# MD201x_2019-09-04.net
KiCad netlist of a schematic drawn in EAGLE
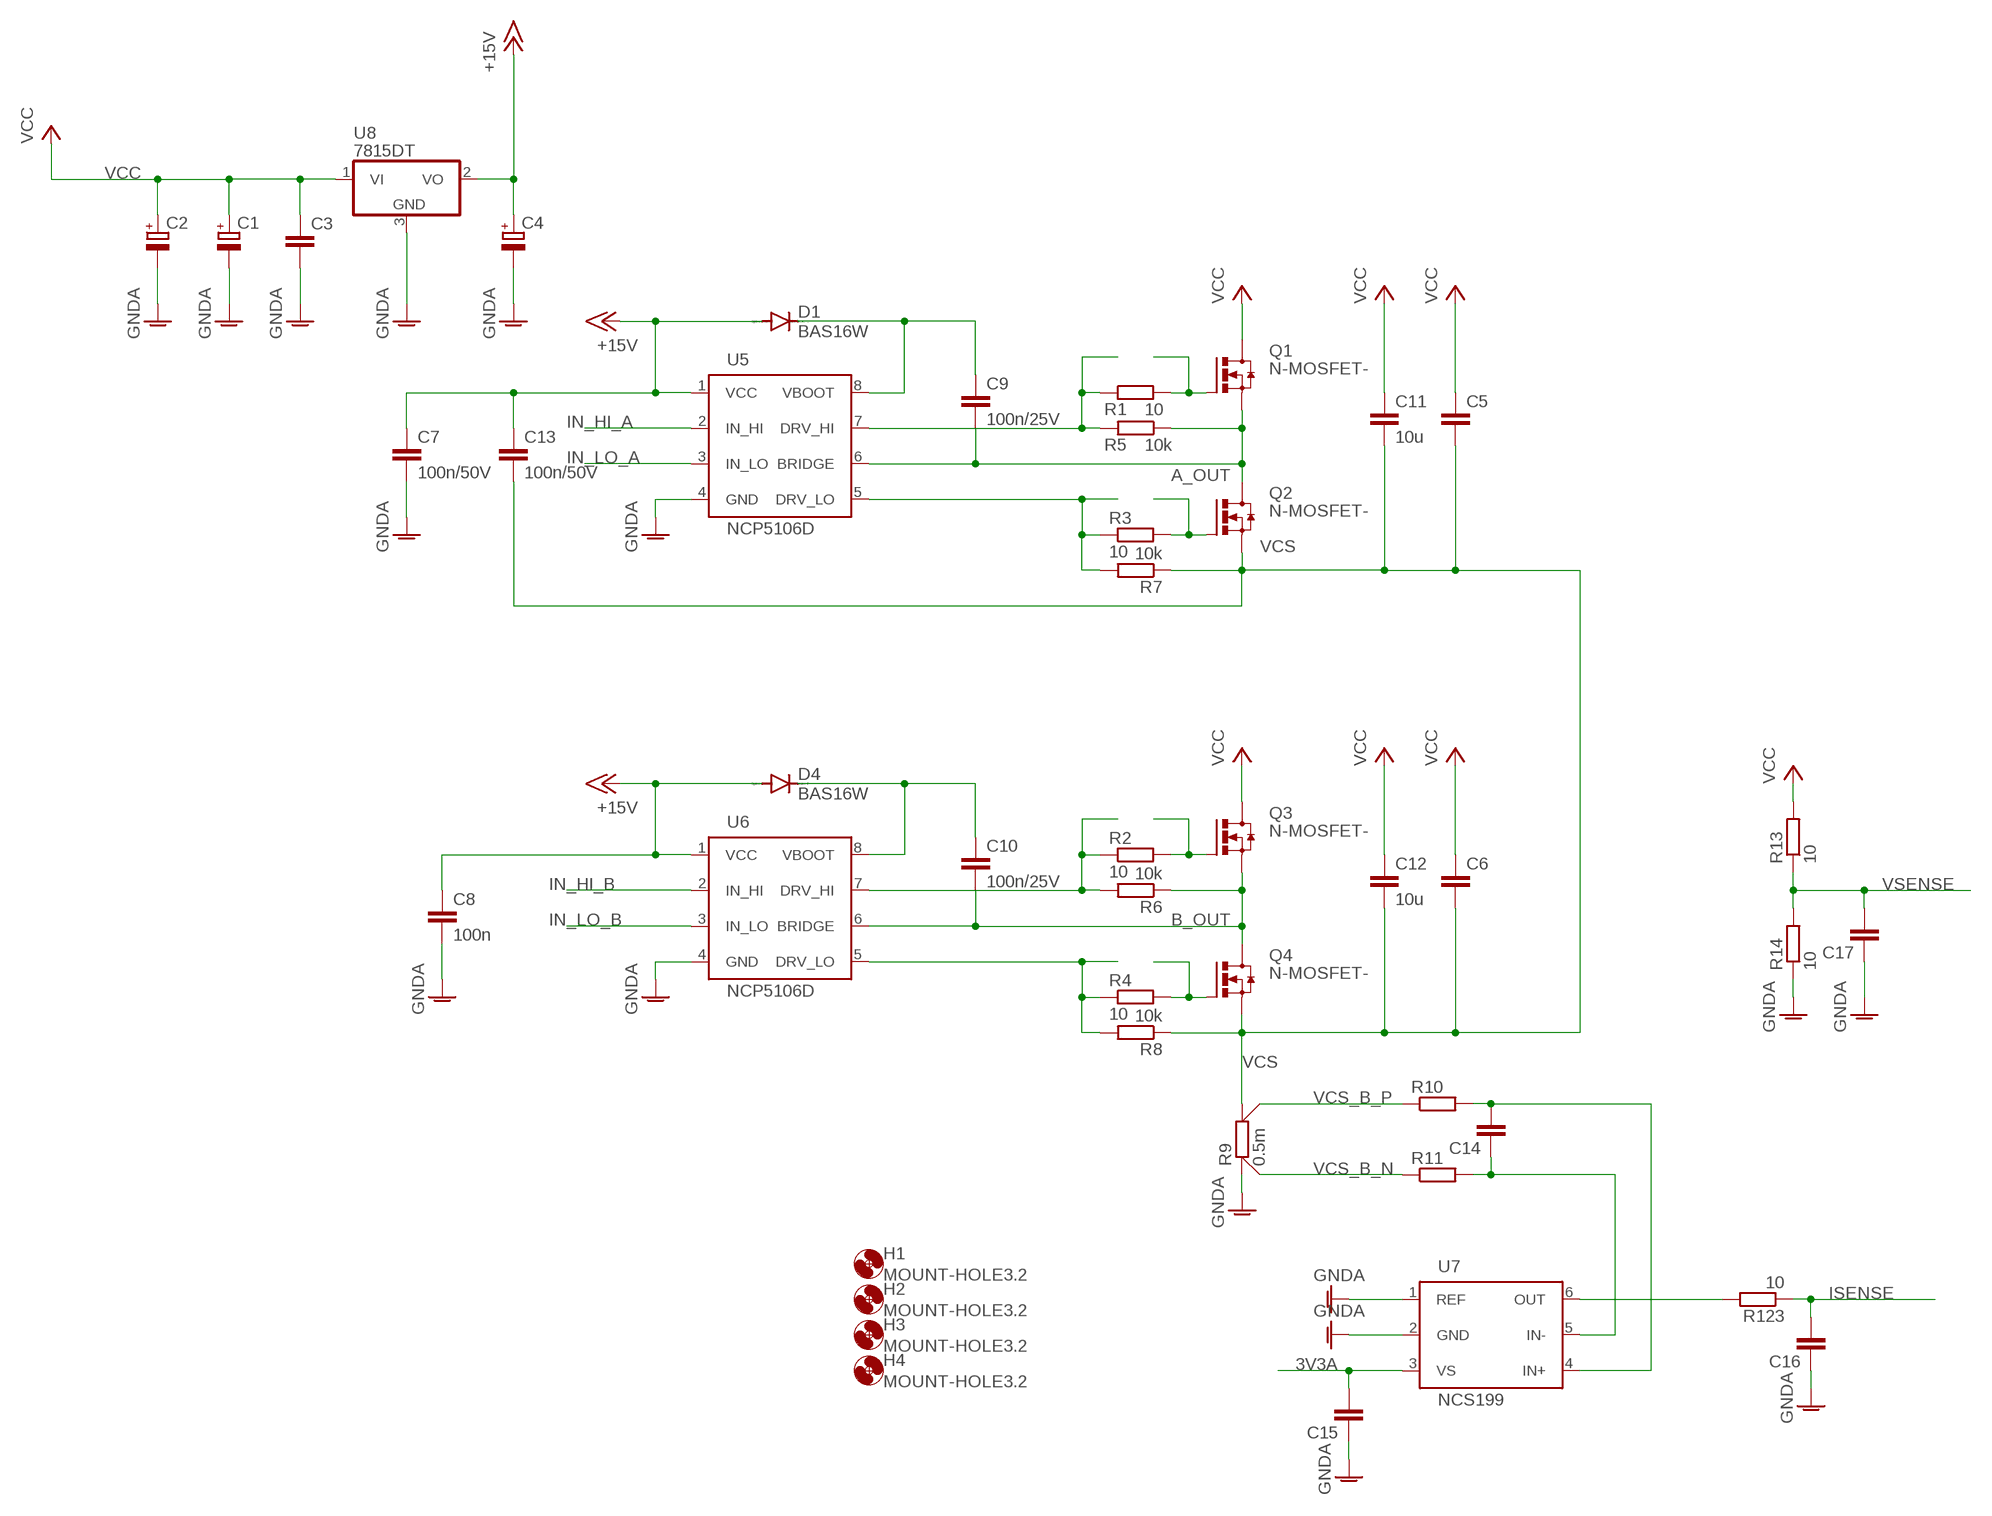
[diagram p0: schematic, sheet 1]
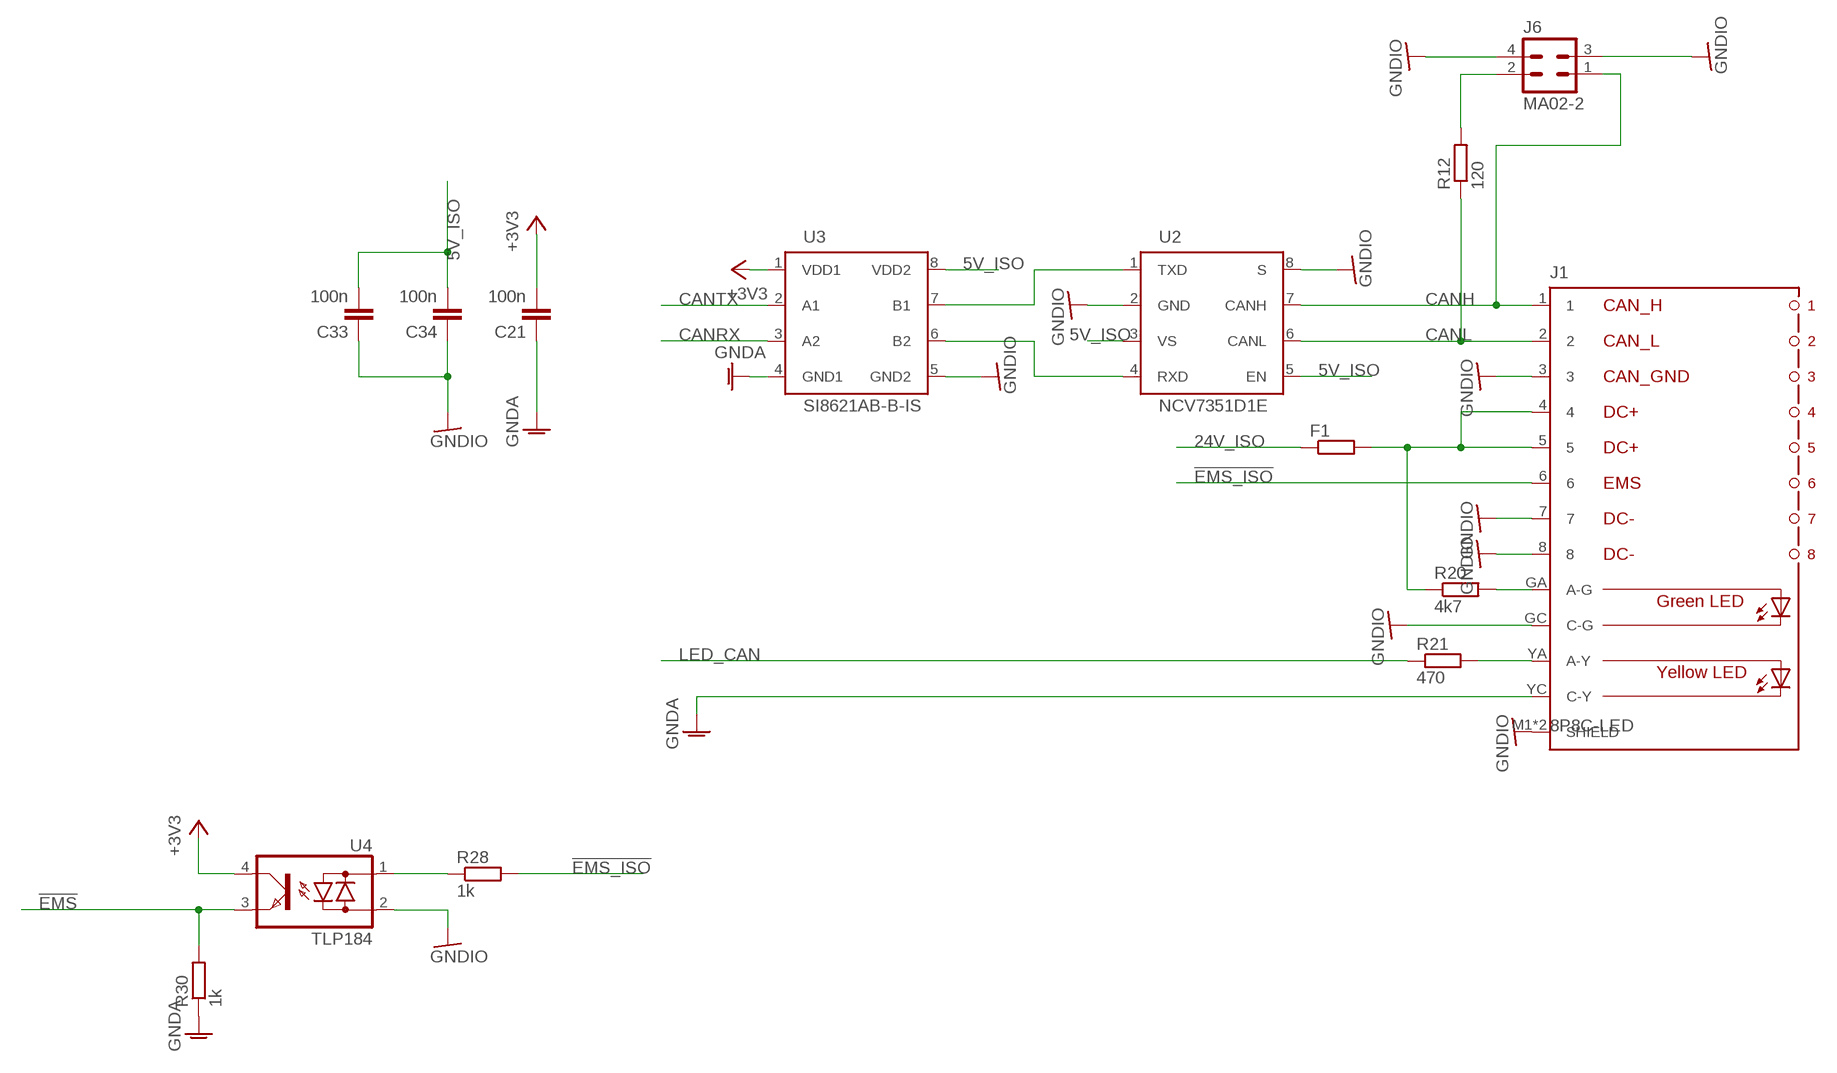
[diagram p1: schematic, sheet 2]
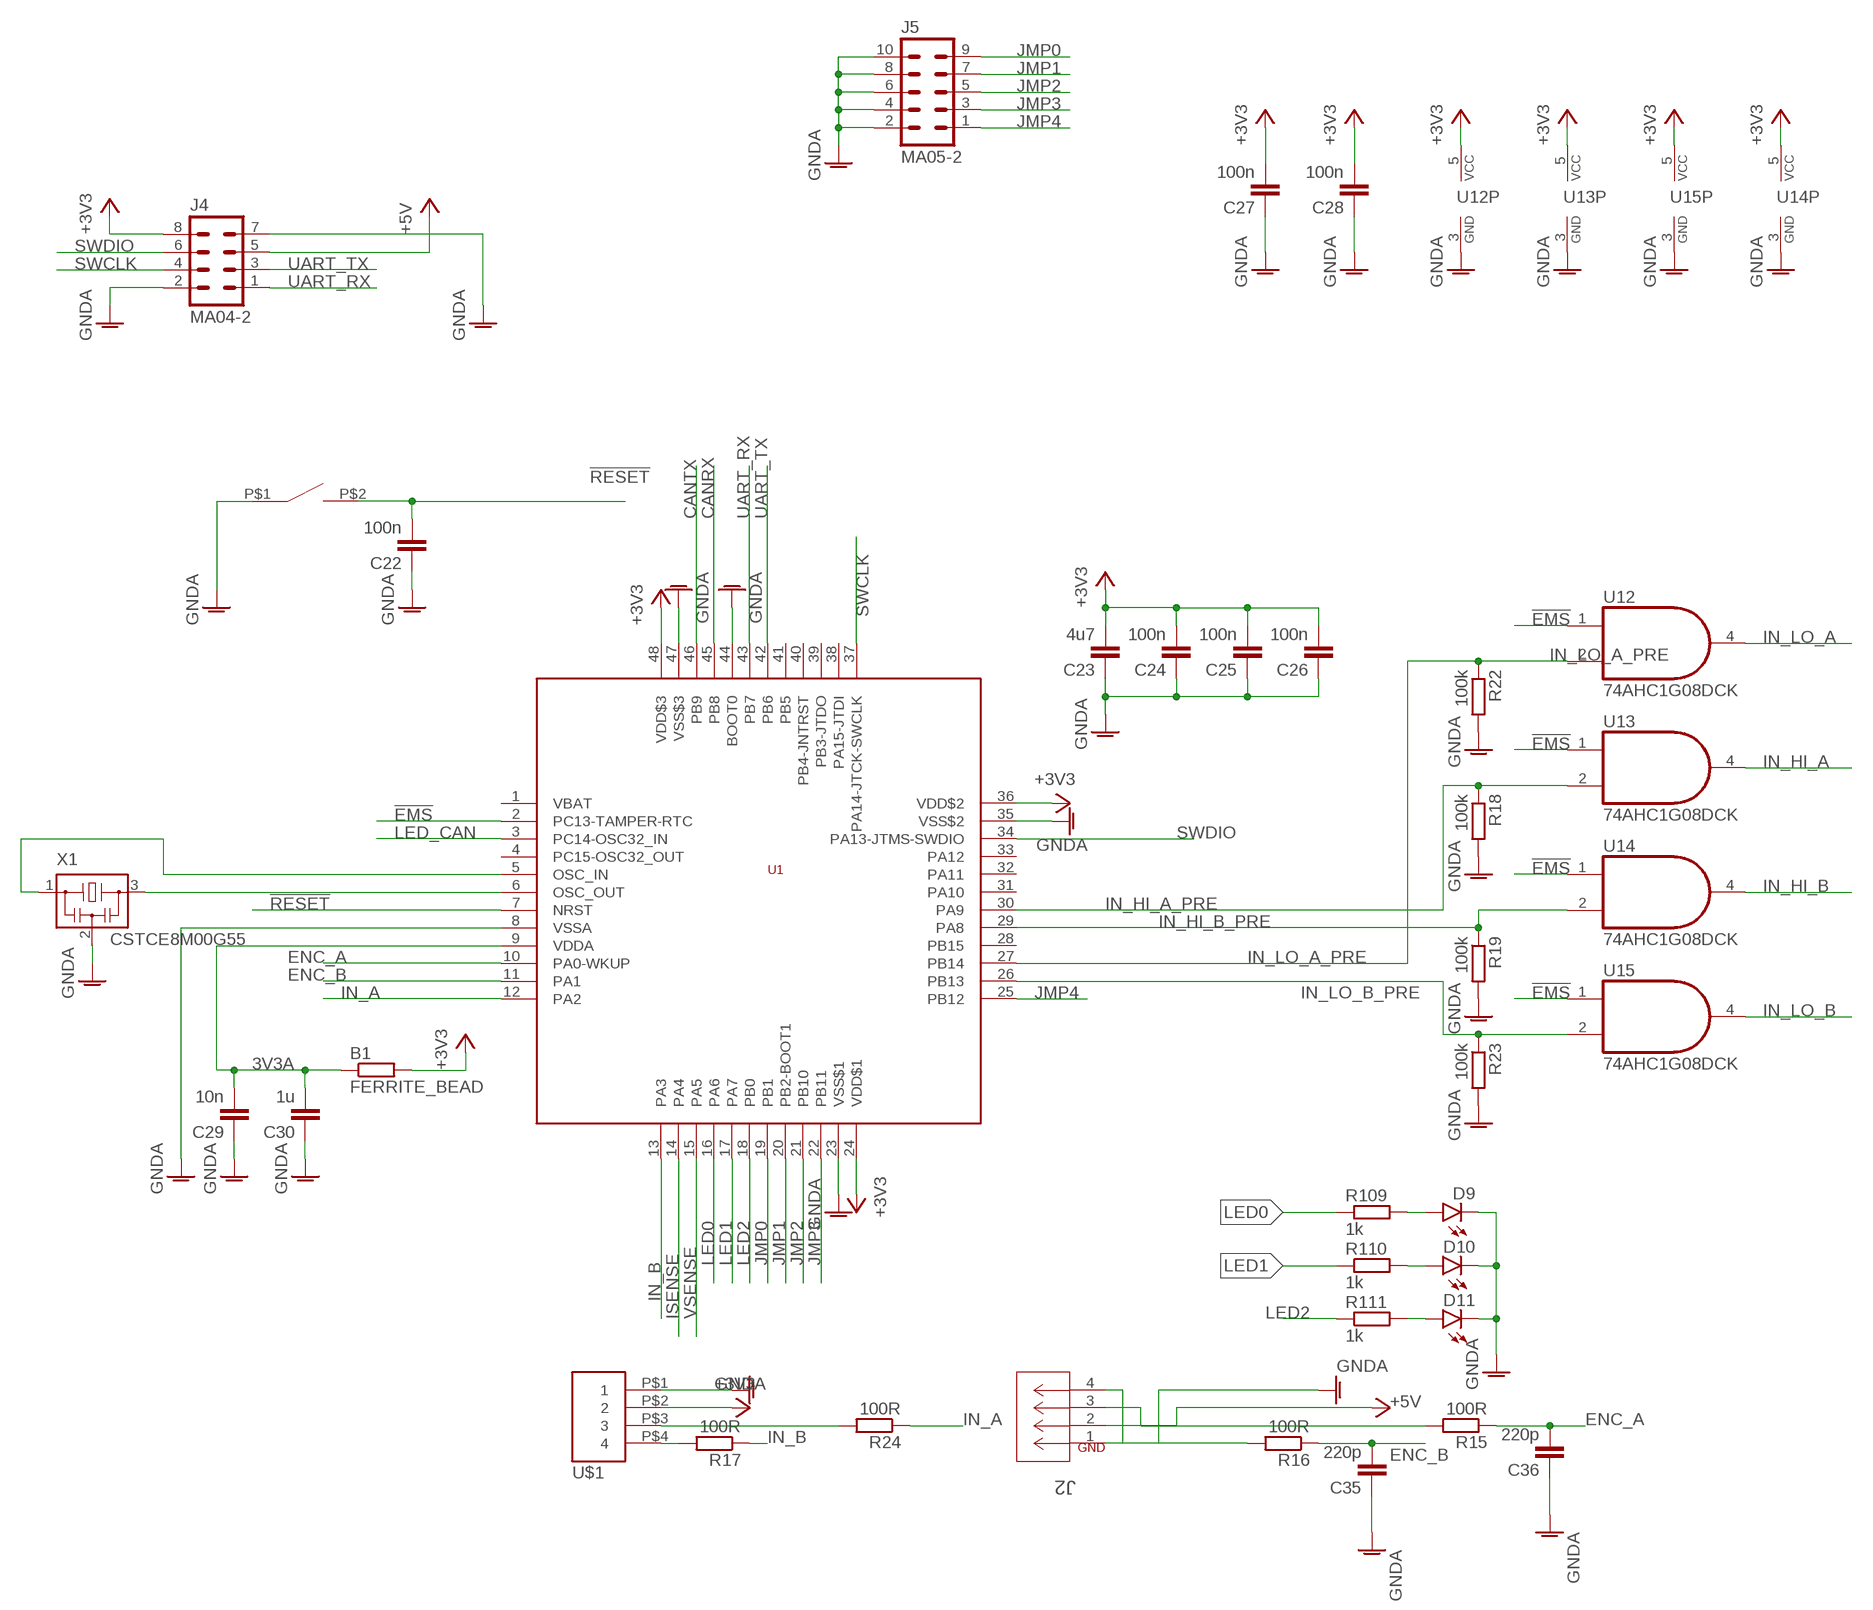
[diagram p2: schematic, sheet 3]
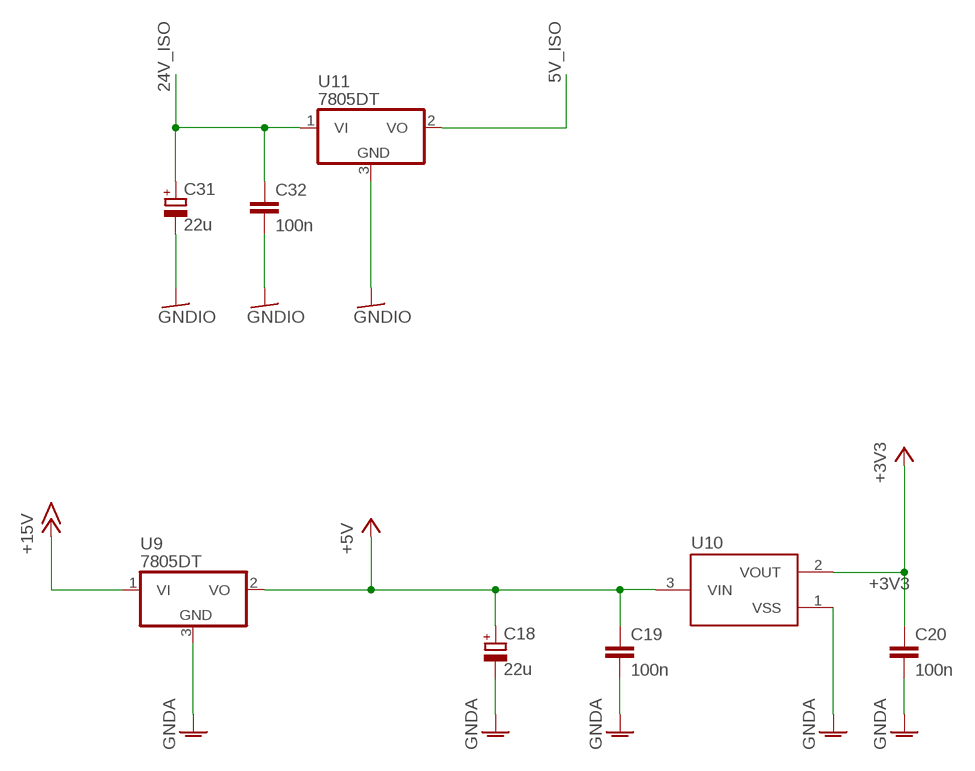
[diagram p3: schematic, sheet 4]

(export (version "E")
  (design (tool "Eeschema 10.0.6"))
  (components
    (comp (ref "C21")
      (value "100n")
      (footprint "eagle-import:C0603")
      (libsource (lib "eagle-import") (part "C-EUC0603"))
    )
    (comp (ref "C33")
      (value "100n")
      (footprint "eagle-import:C0805")
      (libsource (lib "eagle-import") (part "C-EUC0805"))
    )
    (comp (ref "C34")
      (value "100n")
      (footprint "eagle-import:C0603")
      (libsource (lib "eagle-import") (part "C-EUC0603"))
    )
    (comp (ref "F1")
      (value "R-EU_R1206")
      (footprint "eagle-import:R1206")
      (libsource (lib "eagle-import") (part "rcl_334_R-EU_R1206"))
    )
    (comp (ref "J1")
      (value "8P8C-LED")
      (footprint "eagle-import:8P8C-LED")
      (libsource (lib "eagle-import") (part "8P8C-LED"))
    )
    (comp (ref "J6")
      (value "MA02-2")
      (footprint "eagle-import:MA02-2W")
      (libsource (lib "eagle-import") (part "MA02-2"))
    )
    (comp (ref "R12")
      (value "120")
      (footprint "eagle-import:R0603")
      (libsource (lib "eagle-import") (part "rcl_334_R-EU_R0603"))
    )
    (comp (ref "R20")
      (value "4k7")
      (footprint "eagle-import:R0603")
      (libsource (lib "eagle-import") (part "rcl_334_R-EU_R0603"))
    )
    (comp (ref "R21")
      (value "470")
      (footprint "eagle-import:R0603")
      (libsource (lib "eagle-import") (part "rcl_334_R-EU_R0603"))
    )
    (comp (ref "R28")
      (value "1k")
      (footprint "eagle-import:R0603")
      (libsource (lib "eagle-import") (part "rcl_334_R-EU_R0603"))
    )
    (comp (ref "R30")
      (value "1k")
      (footprint "eagle-import:R0603")
      (libsource (lib "eagle-import") (part "rcl_334_R-EU_R0603"))
    )
    (comp (ref "U2")
      (value "NCV7351D1E")
      (footprint "eagle-import:SO08")
      (libsource (lib "eagle-import") (part "NCV7351D1E"))
    )
    (comp (ref "U3")
      (value "SI8621AB-B-IS")
      (footprint "eagle-import:SO08")
      (libsource (lib "eagle-import") (part "SI8621AB-B-IS"))
    )
    (comp (ref "U4")
      (value "TLP184")
      (footprint "eagle-import:11-4M1S")
      (libsource (lib "eagle-import") (part "TLP184"))
    )
    (comp (ref "C18")
      (value "22u")
      (footprint "eagle-import:E2,5-5")
      (libsource (lib "eagle-import") (part "CPOL-EUE2.5-5"))
    )
    (comp (ref "C19")
      (value "100n")
      (footprint "eagle-import:C0603")
      (libsource (lib "eagle-import") (part "C-EUC0603"))
    )
    (comp (ref "C20")
      (value "100n")
      (footprint "eagle-import:C0603")
      (libsource (lib "eagle-import") (part "C-EUC0603"))
    )
    (comp (ref "C31")
      (value "22u")
      (footprint "eagle-import:E2,5-5")
      (libsource (lib "eagle-import") (part "CPOL-EUE2.5-5"))
    )
    (comp (ref "C32")
      (value "100n")
      (footprint "eagle-import:C0603")
      (libsource (lib "eagle-import") (part "C-EUC0603"))
    )
    (comp (ref "U9")
      (value "7805DT")
      (footprint "eagle-import:TO252")
      (libsource (lib "eagle-import") (part "78DT05"))
    )
    (comp (ref "U10")
      (value "XC6206")
      (footprint "eagle-import:SOT95P240X110-3")
      (libsource (lib "eagle-import") (part "XC6206"))
    )
    (comp (ref "U11")
      (value "7805DT")
      (footprint "eagle-import:TO252")
      (libsource (lib "eagle-import") (part "78DT05"))
    )
    (comp (ref "B1")
      (value "FERRITE_BEAD")
      (footprint "eagle-import:R0603")
      (libsource (lib "eagle-import") (part "R-EU_R0603"))
    )
    (comp (ref "C22")
      (value "100n")
      (footprint "eagle-import:C0603")
      (libsource (lib "eagle-import") (part "C-EUC0603"))
    )
    (comp (ref "C23")
      (value "4u7")
      (footprint "eagle-import:C0805")
      (libsource (lib "eagle-import") (part "C-EUC0805"))
    )
    (comp (ref "C24")
      (value "100n")
      (footprint "eagle-import:C0603")
      (libsource (lib "eagle-import") (part "C-EUC0603"))
    )
    (comp (ref "C25")
      (value "100n")
      (footprint "eagle-import:C0603")
      (libsource (lib "eagle-import") (part "C-EUC0603"))
    )
    (comp (ref "C26")
      (value "100n")
      (footprint "eagle-import:C0603")
      (libsource (lib "eagle-import") (part "C-EUC0603"))
    )
    (comp (ref "C27")
      (value "100n")
      (footprint "eagle-import:C0603")
      (libsource (lib "eagle-import") (part "C-EUC0603"))
    )
    (comp (ref "C28")
      (value "100n")
      (footprint "eagle-import:C0603")
      (libsource (lib "eagle-import") (part "C-EUC0603"))
    )
    (comp (ref "C29")
      (value "10n")
      (footprint "eagle-import:C0603")
      (libsource (lib "eagle-import") (part "C-EUC0603"))
    )
    (comp (ref "C30")
      (value "1u")
      (footprint "eagle-import:C0603")
      (libsource (lib "eagle-import") (part "C-EUC0603"))
    )
    (comp (ref "C35")
      (value "220p")
      (footprint "eagle-import:C0603")
      (libsource (lib "eagle-import") (part "C-EUC0603"))
    )
    (comp (ref "C36")
      (value "220p")
      (footprint "eagle-import:C0603")
      (libsource (lib "eagle-import") (part "C-EUC0603"))
    )
    (comp (ref "D9")
      (value "LEDCHIPLED_0805")
      (footprint "eagle-import:CHIPLED_0805")
      (libsource (lib "eagle-import") (part "LEDCHIPLED_0805"))
    )
    (comp (ref "D10")
      (value "LEDCHIPLED_0805")
      (footprint "eagle-import:CHIPLED_0805")
      (libsource (lib "eagle-import") (part "LEDCHIPLED_0805"))
    )
    (comp (ref "D11")
      (value "LEDCHIPLED_0805")
      (footprint "eagle-import:CHIPLED_0805")
      (libsource (lib "eagle-import") (part "LEDCHIPLED_0805"))
    )
    (comp (ref "J2")
      (value "1744426-4")
      (footprint "eagle-import:CONN4_1744426-4")
      (fields (field (name "MANUFACTURER_PART_NUMBER") "17444264"))
      (libsource (lib "eagle-import") (part "1744426-4"))
    )
    (comp (ref "J4")
      (value "MA04-2")
      (footprint "eagle-import:MA04-2W")
      (libsource (lib "eagle-import") (part "MA04-2"))
    )
    (comp (ref "J5")
      (value "MA05-2")
      (footprint "eagle-import:MA05-2W")
      (libsource (lib "eagle-import") (part "MA05-2"))
    )
    (comp (ref "R15")
      (value "100R")
      (footprint "eagle-import:R0603")
      (libsource (lib "eagle-import") (part "R-EU_R0603"))
    )
    (comp (ref "R16")
      (value "100R")
      (footprint "eagle-import:R0603")
      (libsource (lib "eagle-import") (part "R-EU_R0603"))
    )
    (comp (ref "R17")
      (value "100R")
      (footprint "eagle-import:R0603")
      (libsource (lib "eagle-import") (part "R-EU_R0603"))
    )
    (comp (ref "R18")
      (value "100k")
      (footprint "eagle-import:R0603")
      (libsource (lib "eagle-import") (part "R-EU_R0603"))
    )
    (comp (ref "R19")
      (value "100k")
      (footprint "eagle-import:R0603")
      (libsource (lib "eagle-import") (part "R-EU_R0603"))
    )
    (comp (ref "R22")
      (value "100k")
      (footprint "eagle-import:R0603")
      (libsource (lib "eagle-import") (part "R-EU_R0603"))
    )
    (comp (ref "R23")
      (value "100k")
      (footprint "eagle-import:R0603")
      (libsource (lib "eagle-import") (part "R-EU_R0603"))
    )
    (comp (ref "R24")
      (value "100R")
      (footprint "eagle-import:R0603")
      (libsource (lib "eagle-import") (part "R-EU_R0603"))
    )
    (comp (ref "R109")
      (value "1k")
      (footprint "eagle-import:R0603")
      (libsource (lib "eagle-import") (part "R-EU_R0603"))
    )
    (comp (ref "R110")
      (value "1k")
      (footprint "eagle-import:R0603")
      (libsource (lib "eagle-import") (part "R-EU_R0603"))
    )
    (comp (ref "R111")
      (value "1k")
      (footprint "eagle-import:R0603")
      (libsource (lib "eagle-import") (part "R-EU_R0603"))
    )
    (comp (ref "S1")
      (value "SWITCH_TACTILETOP")
      (footprint "eagle-import:SWITCH_TACTILE_3X6")
      (libsource (lib "eagle-import") (part "SWITCH_TACTILETOP"))
    )
    (comp (ref "U$1")
      (value "XH-4-SIDE")
      (footprint "eagle-import:CON-XH-4-SIDE")
      (libsource (lib "eagle-import") (part "XH-4-SIDE"))
    )
    (comp (ref "U1")
      (value "STM32F103C8")
      (footprint "eagle-import:LQFP48")
      (libsource (lib "eagle-import") (part "STM32F103C8"))
    )
    (comp (ref "U12")
      (value "74AHC1G08DCK")
      (footprint "eagle-import:SC70-5")
      (libsource (lib "eagle-import") (part "741G08DCKAHC"))
    )
    (comp (ref "U13")
      (value "74AHC1G08DCK")
      (footprint "eagle-import:SC70-5")
      (libsource (lib "eagle-import") (part "741G08DCKAHC"))
    )
    (comp (ref "U14")
      (value "74AHC1G08DCK")
      (footprint "eagle-import:SC70-5")
      (libsource (lib "eagle-import") (part "741G08DCKAHC"))
    )
    (comp (ref "U15")
      (value "74AHC1G08DCK")
      (footprint "eagle-import:SC70-5")
      (libsource (lib "eagle-import") (part "741G08DCKAHC"))
    )
    (comp (ref "X1")
      (value "CSTCE8M00G55")
      (footprint "eagle-import:CSTCE8M00G55")
      (libsource (lib "eagle-import") (part "CSTCE8M00G55"))
    )
    (comp (ref "C1")
      (value "CPOL-EUE5-10.5")
      (footprint "eagle-import:E5-10,5")
      (libsource (lib "eagle-import") (part "CPOL-EUE5-10.5"))
    )
    (comp (ref "C2")
      (value "CPOL-EUE5-10.5")
      (footprint "eagle-import:E5-10,5")
      (libsource (lib "eagle-import") (part "CPOL-EUE5-10.5"))
    )
    (comp (ref "C3")
      (value "C-EUC0603")
      (footprint "eagle-import:C0603")
      (libsource (lib "eagle-import") (part "C-EUC0603"))
    )
    (comp (ref "C4")
      (value "CPOL-EUE2.5-5")
      (footprint "eagle-import:E2,5-5")
      (libsource (lib "eagle-import") (part "CPOL-EUE2.5-5"))
    )
    (comp (ref "C5")
      (value "C-EUC0603")
      (footprint "eagle-import:C0603")
      (libsource (lib "eagle-import") (part "C-EUC0603"))
    )
    (comp (ref "C6")
      (value "C-EUC0603")
      (footprint "eagle-import:C0603")
      (libsource (lib "eagle-import") (part "C-EUC0603"))
    )
    (comp (ref "C7")
      (value "100n/50V")
      (footprint "eagle-import:C0603")
      (libsource (lib "eagle-import") (part "C-EUC0603"))
    )
    (comp (ref "C8")
      (value "100n")
      (footprint "eagle-import:C0603")
      (libsource (lib "eagle-import") (part "C-EUC0603"))
    )
    (comp (ref "C9")
      (value "100n/25V")
      (footprint "eagle-import:C0603")
      (libsource (lib "eagle-import") (part "C-EUC0603"))
    )
    (comp (ref "C10")
      (value "100n/25V")
      (footprint "eagle-import:C0603")
      (libsource (lib "eagle-import") (part "C-EUC0603"))
    )
    (comp (ref "C11")
      (value "10u")
      (footprint "eagle-import:C1210")
      (libsource (lib "eagle-import") (part "C-EUC1210"))
    )
    (comp (ref "C12")
      (value "10u")
      (footprint "eagle-import:C1210")
      (libsource (lib "eagle-import") (part "C-EUC1210"))
    )
    (comp (ref "C13")
      (value "100n/50V")
      (footprint "eagle-import:C0603")
      (libsource (lib "eagle-import") (part "C-EUC0603"))
    )
    (comp (ref "C14")
      (value "C-EUC0603")
      (footprint "eagle-import:C0603")
      (libsource (lib "eagle-import") (part "rcl_334_C-EUC0603"))
    )
    (comp (ref "C15")
      (value "C-EUC0603")
      (footprint "eagle-import:C0603")
      (libsource (lib "eagle-import") (part "rcl_334_C-EUC0603"))
    )
    (comp (ref "C16")
      (value "C-EUC0603")
      (footprint "eagle-import:C0603")
      (libsource (lib "eagle-import") (part "rcl_334_C-EUC0603"))
    )
    (comp (ref "C17")
      (value "C-EUC0603")
      (footprint "eagle-import:C0603")
      (libsource (lib "eagle-import") (part "rcl_334_C-EUC0603"))
    )
    (comp (ref "D1")
      (value "BAS16W")
      (footprint "eagle-import:SOD323-R")
      (libsource (lib "eagle-import") (part "DIODE-SOD323-R"))
    )
    (comp (ref "D4")
      (value "BAS16W")
      (footprint "eagle-import:SOD323-R")
      (libsource (lib "eagle-import") (part "DIODE-SOD323-R"))
    )
    (comp (ref "H1")
      (value "MOUNT-HOLE3.2")
      (footprint "eagle-import:3,2")
      (libsource (lib "eagle-import") (part "MOUNT-HOLE3.2"))
    )
    (comp (ref "H2")
      (value "MOUNT-HOLE3.2")
      (footprint "eagle-import:3,2")
      (libsource (lib "eagle-import") (part "MOUNT-HOLE3.2"))
    )
    (comp (ref "H3")
      (value "MOUNT-HOLE3.2")
      (footprint "eagle-import:3,2")
      (libsource (lib "eagle-import") (part "MOUNT-HOLE3.2"))
    )
    (comp (ref "H4")
      (value "MOUNT-HOLE3.2")
      (footprint "eagle-import:3,2")
      (libsource (lib "eagle-import") (part "MOUNT-HOLE3.2"))
    )
    (comp (ref "Q1")
      (value "N-MOSFET-")
      (footprint "eagle-import:SOT669")
      (libsource (lib "eagle-import") (part "N-MOSFET-"))
    )
    (comp (ref "Q2")
      (value "N-MOSFET-")
      (footprint "eagle-import:SOT669")
      (libsource (lib "eagle-import") (part "N-MOSFET-"))
    )
    (comp (ref "Q3")
      (value "N-MOSFET-")
      (footprint "eagle-import:SOT669")
      (libsource (lib "eagle-import") (part "N-MOSFET-"))
    )
    (comp (ref "Q4")
      (value "N-MOSFET-")
      (footprint "eagle-import:SOT669")
      (libsource (lib "eagle-import") (part "N-MOSFET-"))
    )
    (comp (ref "R1")
      (value "10")
      (footprint "eagle-import:R0603")
      (libsource (lib "eagle-import") (part "R-EU_R0603"))
    )
    (comp (ref "R2")
      (value "10")
      (footprint "eagle-import:R0603")
      (libsource (lib "eagle-import") (part "R-EU_R0603"))
    )
    (comp (ref "R3")
      (value "10")
      (footprint "eagle-import:R0603")
      (libsource (lib "eagle-import") (part "R-EU_R0603"))
    )
    (comp (ref "R4")
      (value "10")
      (footprint "eagle-import:R0603")
      (libsource (lib "eagle-import") (part "R-EU_R0603"))
    )
    (comp (ref "R5")
      (value "10k")
      (footprint "eagle-import:R0603")
      (libsource (lib "eagle-import") (part "R-EU_R0603"))
    )
    (comp (ref "R6")
      (value "10k")
      (footprint "eagle-import:R0603")
      (libsource (lib "eagle-import") (part "R-EU_R0603"))
    )
    (comp (ref "R7")
      (value "10k")
      (footprint "eagle-import:R0603")
      (libsource (lib "eagle-import") (part "R-EU_R0603"))
    )
    (comp (ref "R8")
      (value "10k")
      (footprint "eagle-import:R0603")
      (libsource (lib "eagle-import") (part "R-EU_R0603"))
    )
    (comp (ref "R9")
      (value "0.5m")
      (footprint "eagle-import:CSS2H-2512")
      (libsource (lib "eagle-import") (part "CSS2H-2512"))
    )
    (comp (ref "R10")
      (value "R-EU_R0603")
      (footprint "eagle-import:R0603")
      (libsource (lib "eagle-import") (part "rcl_334_R-EU_R0603"))
    )
    (comp (ref "R11")
      (value "R-EU_R0603")
      (footprint "eagle-import:R0603")
      (libsource (lib "eagle-import") (part "rcl_334_R-EU_R0603"))
    )
    (comp (ref "R13")
      (value "10")
      (footprint "eagle-import:R0603")
      (libsource (lib "eagle-import") (part "R-EU_R0603"))
    )
    (comp (ref "R14")
      (value "10")
      (footprint "eagle-import:R0603")
      (libsource (lib "eagle-import") (part "R-EU_R0603"))
    )
    (comp (ref "R123")
      (value "10")
      (footprint "eagle-import:R0603")
      (libsource (lib "eagle-import") (part "R-EU_R0603"))
    )
    (comp (ref "U5")
      (value "NCP5106D")
      (footprint "eagle-import:SOIC127P600X175-8")
      (libsource (lib "eagle-import") (part "NCP5106D"))
    )
    (comp (ref "U6")
      (value "NCP5106D")
      (footprint "eagle-import:SOIC127P600X175-8")
      (libsource (lib "eagle-import") (part "NCP5106D"))
    )
    (comp (ref "U7")
      (value "NCS199")
      (footprint "eagle-import:SOT65P210X110-6")
      (libsource (lib "eagle-import") (part "NCS199"))
    )
    (comp (ref "U8")
      (value "7815DT")
      (footprint "eagle-import:TO252")
      (libsource (lib "eagle-import") (part "78DT15"))
    )
  )
  (nets
    (net (code "1") (name "+3V3") (class "Default")
      (node (ref "B1") (pin "2") (pinfunction "2_2") (pintype "passive"))
      (node (ref "C20") (pin "1") (pinfunction "1_1") (pintype "passive"))
      (node (ref "C21") (pin "2") (pinfunction "2_2") (pintype "passive"))
      (node (ref "C23") (pin "2") (pinfunction "2_2") (pintype "passive"))
      (node (ref "C24") (pin "2") (pinfunction "2_2") (pintype "passive"))
      (node (ref "C25") (pin "2") (pinfunction "2_2") (pintype "passive"))
      (node (ref "C26") (pin "2") (pinfunction "2_2") (pintype "passive"))
      (node (ref "C27") (pin "2") (pinfunction "2_2") (pintype "passive"))
      (node (ref "C28") (pin "2") (pinfunction "2_2") (pintype "passive"))
      (node (ref "J4") (pin "8") (pinfunction "8_8") (pintype "passive"))
      (node (ref "U$1") (pin "P$2") (pinfunction "2_P$2") (pintype "bidirectional"))
      (node (ref "U1") (pin "24") (pinfunction "VDD$1_24") (pintype "passive"))
      (node (ref "U1") (pin "36") (pinfunction "VDD$2_36") (pintype "passive"))
      (node (ref "U1") (pin "48") (pinfunction "VDD$3_48") (pintype "passive"))
      (node (ref "U10") (pin "2") (pinfunction "VOUT_2") (pintype "bidirectional"))
      (node (ref "U12") (pin "5") (pinfunction "VCC_5") (pintype "power_in"))
      (node (ref "U13") (pin "5") (pinfunction "VCC_5") (pintype "power_in"))
      (node (ref "U14") (pin "5") (pinfunction "VCC_5") (pintype "power_in"))
      (node (ref "U15") (pin "5") (pinfunction "VCC_5") (pintype "power_in"))
      (node (ref "U3") (pin "1") (pinfunction "VDD1_1") (pintype "power_in"))
      (node (ref "U4") (pin "4") (pinfunction "C_4") (pintype "passive"))
    )
    (net (code "2") (name "+5V") (class "Default")
      (node (ref "C18") (pin "+") (pinfunction "+_+") (pintype "passive"))
      (node (ref "C19") (pin "1") (pinfunction "1_1") (pintype "passive"))
      (node (ref "J2") (pin "2") (pinfunction "2_2") (pintype "passive"))
      (node (ref "J4") (pin "5") (pinfunction "5_5") (pintype "passive"))
      (node (ref "U10") (pin "3") (pinfunction "VIN_3") (pintype "bidirectional"))
      (node (ref "U9") (pin "2") (pinfunction "VO_2") (pintype "passive"))
    )
    (net (code "3") (name "+15V") (class "Default")
      (node (ref "C13") (pin "1") (pinfunction "1_1") (pintype "passive"))
      (node (ref "C4") (pin "+") (pinfunction "+_+") (pintype "passive"))
      (node (ref "C7") (pin "1") (pinfunction "1_1") (pintype "passive"))
      (node (ref "C8") (pin "1") (pinfunction "1_1") (pintype "passive"))
      (node (ref "D1") (pin "A") (pinfunction "A_A") (pintype "passive"))
      (node (ref "D4") (pin "A") (pinfunction "A_A") (pintype "passive"))
      (node (ref "U5") (pin "1") (pinfunction "VCC_1") (pintype "power_in"))
      (node (ref "U6") (pin "1") (pinfunction "VCC_1") (pintype "power_in"))
      (node (ref "U8") (pin "2") (pinfunction "VO_2") (pintype "passive"))
      (node (ref "U9") (pin "1") (pinfunction "VI_1") (pintype "input"))
    )
    (net (code "4") (name "3V3A") (class "Default")
      (node (ref "B1") (pin "1") (pinfunction "1_1") (pintype "passive"))
      (node (ref "C15") (pin "2") (pinfunction "2_2") (pintype "passive"))
      (node (ref "C29") (pin "2") (pinfunction "2_2") (pintype "passive"))
      (node (ref "C30") (pin "2") (pinfunction "2_2") (pintype "passive"))
      (node (ref "U1") (pin "9") (pinfunction "VDDA_9") (pintype "bidirectional"))
      (node (ref "U7") (pin "3") (pinfunction "VS_3") (pintype "power_in"))
    )
    (net (code "5") (name "5V_ISO") (class "Default")
      (node (ref "C33") (pin "2") (pinfunction "2_2") (pintype "passive"))
      (node (ref "C34") (pin "2") (pinfunction "2_2") (pintype "passive"))
      (node (ref "U11") (pin "2") (pinfunction "VO_2") (pintype "passive"))
      (node (ref "U2") (pin "3") (pinfunction "VS_3") (pintype "power_in"))
      (node (ref "U2") (pin "5") (pinfunction "EN_5") (pintype "input"))
      (node (ref "U3") (pin "8") (pinfunction "VDD2_8") (pintype "power_in"))
    )
    (net (code "6") (name "24V_ISO") (class "Default")
      (node (ref "C31") (pin "+") (pinfunction "+_+") (pintype "passive"))
      (node (ref "C32") (pin "1") (pinfunction "1_1") (pintype "passive"))
      (node (ref "F1") (pin "1") (pinfunction "1_1") (pintype "passive"))
      (node (ref "U11") (pin "1") (pinfunction "VI_1") (pintype "input"))
    )
    (net (code "7") (name "A_OUT") (class "Default")
      (node (ref "C9") (pin "2") (pinfunction "2_2") (pintype "passive"))
      (node (ref "Q1") (pin "1") (pinfunction "SOURCE_1") (pintype "passive"))
      (node (ref "Q1") (pin "2") (pinfunction "SOURCE_2") (pintype "passive"))
      (node (ref "Q1") (pin "3") (pinfunction "SOURCE_3") (pintype "passive"))
      (node (ref "Q2") (pin "5") (pinfunction "DRAIN_5") (pintype "passive"))
      (node (ref "R5") (pin "1") (pinfunction "1_1") (pintype "passive"))
      (node (ref "U5") (pin "6") (pinfunction "BRIDGE_6") (pintype "power_in"))
    )
    (net (code "8") (name "B_OUT") (class "Default")
      (node (ref "C10") (pin "2") (pinfunction "2_2") (pintype "passive"))
      (node (ref "Q3") (pin "1") (pinfunction "SOURCE_1") (pintype "passive"))
      (node (ref "Q3") (pin "2") (pinfunction "SOURCE_2") (pintype "passive"))
      (node (ref "Q3") (pin "3") (pinfunction "SOURCE_3") (pintype "passive"))
      (node (ref "Q4") (pin "5") (pinfunction "DRAIN_5") (pintype "passive"))
      (node (ref "R6") (pin "1") (pinfunction "1_1") (pintype "passive"))
      (node (ref "U6") (pin "6") (pinfunction "BRIDGE_6") (pintype "power_in"))
    )
    (net (code "9") (name "CANH") (class "Default")
      (node (ref "J1") (pin "1") (pinfunction "1_1") (pintype "input"))
      (node (ref "J6") (pin "1") (pinfunction "1_1") (pintype "passive"))
      (node (ref "U2") (pin "7") (pinfunction "CANH_7") (pintype "output"))
    )
    (net (code "10") (name "CANL") (class "Default")
      (node (ref "J1") (pin "2") (pinfunction "2_2") (pintype "input"))
      (node (ref "R12") (pin "1") (pinfunction "1_1") (pintype "passive"))
      (node (ref "U2") (pin "6") (pinfunction "CANL_6") (pintype "output"))
    )
    (net (code "11") (name "CANRX") (class "Default")
      (node (ref "U1") (pin "45") (pinfunction "PB8_45") (pintype "bidirectional"))
      (node (ref "U3") (pin "3") (pinfunction "A2_3") (pintype "output"))
    )
    (net (code "12") (name "CANTX") (class "Default")
      (node (ref "U1") (pin "46") (pinfunction "PB9_46") (pintype "bidirectional"))
      (node (ref "U3") (pin "2") (pinfunction "A1_2") (pintype "input"))
    )
    (net (code "13") (name "ENC_A") (class "Default")
      (node (ref "C36") (pin "2") (pinfunction "2_2") (pintype "passive"))
      (node (ref "R15") (pin "1") (pinfunction "1_1") (pintype "passive"))
      (node (ref "U1") (pin "10") (pinfunction "PA0-WKUP_10") (pintype "bidirectional"))
    )
    (net (code "14") (name "ENC_B") (class "Default")
      (node (ref "C35") (pin "2") (pinfunction "2_2") (pintype "passive"))
      (node (ref "R16") (pin "1") (pinfunction "1_1") (pintype "passive"))
      (node (ref "U1") (pin "11") (pinfunction "PA1_11") (pintype "bidirectional"))
    )
    (net (code "15") (name "GNDA") (class "Default")
      (node (ref "C1") (pin "-") (pinfunction "-_-") (pintype "passive"))
      (node (ref "C15") (pin "1") (pinfunction "1_1") (pintype "passive"))
      (node (ref "C16") (pin "1") (pinfunction "1_1") (pintype "passive"))
      (node (ref "C17") (pin "1") (pinfunction "1_1") (pintype "passive"))
      (node (ref "C18") (pin "-") (pinfunction "-_-") (pintype "passive"))
      (node (ref "C19") (pin "2") (pinfunction "2_2") (pintype "passive"))
      (node (ref "C2") (pin "-") (pinfunction "-_-") (pintype "passive"))
      (node (ref "C20") (pin "2") (pinfunction "2_2") (pintype "passive"))
      (node (ref "C21") (pin "1") (pinfunction "1_1") (pintype "passive"))
      (node (ref "C22") (pin "1") (pinfunction "1_1") (pintype "passive"))
      (node (ref "C23") (pin "1") (pinfunction "1_1") (pintype "passive"))
      (node (ref "C24") (pin "1") (pinfunction "1_1") (pintype "passive"))
      (node (ref "C25") (pin "1") (pinfunction "1_1") (pintype "passive"))
      (node (ref "C26") (pin "1") (pinfunction "1_1") (pintype "passive"))
      (node (ref "C27") (pin "1") (pinfunction "1_1") (pintype "passive"))
      (node (ref "C28") (pin "1") (pinfunction "1_1") (pintype "passive"))
      (node (ref "C29") (pin "1") (pinfunction "1_1") (pintype "passive"))
      (node (ref "C3") (pin "2") (pinfunction "2_2") (pintype "passive"))
      (node (ref "C30") (pin "1") (pinfunction "1_1") (pintype "passive"))
      (node (ref "C35") (pin "1") (pinfunction "1_1") (pintype "passive"))
      (node (ref "C36") (pin "1") (pinfunction "1_1") (pintype "passive"))
      (node (ref "C4") (pin "-") (pinfunction "-_-") (pintype "passive"))
      (node (ref "C7") (pin "2") (pinfunction "2_2") (pintype "passive"))
      (node (ref "C8") (pin "2") (pinfunction "2_2") (pintype "passive"))
      (node (ref "D10") (pin "C") (pinfunction "C_C") (pintype "passive"))
      (node (ref "D11") (pin "C") (pinfunction "C_C") (pintype "passive"))
      (node (ref "D9") (pin "C") (pinfunction "C_C") (pintype "passive"))
      (node (ref "J1") (pin "YC") (pinfunction "C-Y_YC") (pintype "passive"))
      (node (ref "J2") (pin "1") (pinfunction "1_1") (pintype "passive"))
      (node (ref "J4") (pin "2") (pinfunction "2_2") (pintype "passive"))
      (node (ref "J4") (pin "7") (pinfunction "7_7") (pintype "passive"))
      (node (ref "J5") (pin "10") (pinfunction "10_10") (pintype "passive"))
      (node (ref "J5") (pin "2") (pinfunction "2_2") (pintype "passive"))
      (node (ref "J5") (pin "4") (pinfunction "4_4") (pintype "passive"))
      (node (ref "J5") (pin "6") (pinfunction "6_6") (pintype "passive"))
      (node (ref "J5") (pin "8") (pinfunction "8_8") (pintype "passive"))
      (node (ref "R14") (pin "1") (pinfunction "1_1") (pintype "passive"))
      (node (ref "R18") (pin "2") (pinfunction "2_2") (pintype "passive"))
      (node (ref "R19") (pin "2") (pinfunction "2_2") (pintype "passive"))
      (node (ref "R22") (pin "2") (pinfunction "2_2") (pintype "passive"))
      (node (ref "R23") (pin "2") (pinfunction "2_2") (pintype "passive"))
      (node (ref "R30") (pin "1") (pinfunction "1_1") (pintype "passive"))
      (node (ref "R9") (pin "1$1") (pinfunction "1_1$1") (pintype "passive"))
      (node (ref "R9") (pin "1$2") (pinfunction "1_1$2") (pintype "passive"))
      (node (ref "S1") (pin "P$1") (pinfunction "1_P$1") (pintype "bidirectional"))
      (node (ref "U$1") (pin "P$1") (pinfunction "1_P$1") (pintype "bidirectional"))
      (node (ref "U1") (pin "23") (pinfunction "VSS$1_23") (pintype "passive"))
      (node (ref "U1") (pin "35") (pinfunction "VSS$2_35") (pintype "passive"))
      (node (ref "U1") (pin "44") (pinfunction "BOOT0_44") (pintype "input"))
      (node (ref "U1") (pin "47") (pinfunction "VSS$3_47") (pintype "passive"))
      (node (ref "U1") (pin "8") (pinfunction "VSSA_8") (pintype "bidirectional"))
      (node (ref "U10") (pin "1") (pinfunction "VSS_1") (pintype "bidirectional"))
      (node (ref "U12") (pin "3") (pinfunction "GND_3") (pintype "power_in"))
      (node (ref "U13") (pin "3") (pinfunction "GND_3") (pintype "power_in"))
      (node (ref "U14") (pin "3") (pinfunction "GND_3") (pintype "power_in"))
      (node (ref "U15") (pin "3") (pinfunction "GND_3") (pintype "power_in"))
      (node (ref "U3") (pin "4") (pinfunction "GND1_4") (pintype "power_in"))
      (node (ref "U5") (pin "4") (pinfunction "GND_4") (pintype "power_in"))
      (node (ref "U6") (pin "4") (pinfunction "GND_4") (pintype "power_in"))
      (node (ref "U7") (pin "1") (pinfunction "REF_1") (pintype "power_in"))
      (node (ref "U7") (pin "2") (pinfunction "GND_2") (pintype "power_in"))
      (node (ref "U8") (pin "3") (pinfunction "GND_3") (pintype "passive"))
      (node (ref "U9") (pin "3") (pinfunction "GND_3") (pintype "passive"))
      (node (ref "X1") (pin "2") (pinfunction "2_2") (pintype "passive"))
    )
    (net (code "16") (name "GNDIO") (class "Default")
      (node (ref "C31") (pin "-") (pinfunction "-_-") (pintype "passive"))
      (node (ref "C32") (pin "2") (pinfunction "2_2") (pintype "passive"))
      (node (ref "C33") (pin "1") (pinfunction "1_1") (pintype "passive"))
      (node (ref "C34") (pin "1") (pinfunction "1_1") (pintype "passive"))
      (node (ref "J1") (pin "3") (pinfunction "3_3") (pintype "input"))
      (node (ref "J1") (pin "7") (pinfunction "7_7") (pintype "input"))
      (node (ref "J1") (pin "8") (pinfunction "8_8") (pintype "input"))
      (node (ref "J1") (pin "GC") (pinfunction "C-G_GC") (pintype "passive"))
      (node (ref "J1") (pin "M1") (pinfunction "SHIELD_M1") (pintype "passive"))
      (node (ref "J1") (pin "M2") (pinfunction "SHIELD_M2") (pintype "passive"))
      (node (ref "J6") (pin "3") (pinfunction "3_3") (pintype "passive"))
      (node (ref "J6") (pin "4") (pinfunction "4_4") (pintype "passive"))
      (node (ref "U11") (pin "3") (pinfunction "GND_3") (pintype "passive"))
      (node (ref "U2") (pin "2") (pinfunction "GND_2") (pintype "power_in"))
      (node (ref "U2") (pin "8") (pinfunction "S_8") (pintype "input"))
      (node (ref "U3") (pin "5") (pinfunction "GND2_5") (pintype "power_in"))
      (node (ref "U4") (pin "2") (pinfunction "AC2_2") (pintype "passive"))
    )
    (net (code "17") (name "IN_A") (class "Default")
      (node (ref "R24") (pin "1") (pinfunction "1_1") (pintype "passive"))
      (node (ref "U1") (pin "12") (pinfunction "PA2_12") (pintype "bidirectional"))
    )
    (net (code "18") (name "IN_B") (class "Default")
      (node (ref "R17") (pin "1") (pinfunction "1_1") (pintype "passive"))
      (node (ref "U1") (pin "13") (pinfunction "PA3_13") (pintype "bidirectional"))
    )
    (net (code "19") (name "IN_HI_A") (class "Default")
      (node (ref "U13") (pin "4") (pinfunction "O_4") (pintype "output"))
      (node (ref "U5") (pin "2") (pinfunction "IN_HI_2") (pintype "input"))
    )
    (net (code "20") (name "IN_HI_A_PRE") (class "Default")
      (node (ref "R18") (pin "1") (pinfunction "1_1") (pintype "passive"))
      (node (ref "U1") (pin "30") (pinfunction "PA9_30") (pintype "bidirectional"))
      (node (ref "U13") (pin "2") (pinfunction "I1_2") (pintype "input"))
    )
    (net (code "21") (name "IN_HI_B") (class "Default")
      (node (ref "U14") (pin "4") (pinfunction "O_4") (pintype "output"))
      (node (ref "U6") (pin "2") (pinfunction "IN_HI_2") (pintype "input"))
    )
    (net (code "22") (name "IN_HI_B_PRE") (class "Default")
      (node (ref "R19") (pin "1") (pinfunction "1_1") (pintype "passive"))
      (node (ref "U1") (pin "29") (pinfunction "PA8_29") (pintype "bidirectional"))
      (node (ref "U14") (pin "2") (pinfunction "I1_2") (pintype "input"))
    )
    (net (code "23") (name "IN_LO_A") (class "Default")
      (node (ref "U12") (pin "4") (pinfunction "O_4") (pintype "output"))
      (node (ref "U5") (pin "3") (pinfunction "IN_LO_3") (pintype "input"))
    )
    (net (code "24") (name "IN_LO_A_PRE") (class "Default")
      (node (ref "R22") (pin "1") (pinfunction "1_1") (pintype "passive"))
      (node (ref "U1") (pin "27") (pinfunction "PB14_27") (pintype "bidirectional"))
      (node (ref "U12") (pin "2") (pinfunction "I1_2") (pintype "input"))
    )
    (net (code "25") (name "IN_LO_B") (class "Default")
      (node (ref "U15") (pin "4") (pinfunction "O_4") (pintype "output"))
      (node (ref "U6") (pin "3") (pinfunction "IN_LO_3") (pintype "input"))
    )
    (net (code "26") (name "IN_LO_B_PRE") (class "Default")
      (node (ref "R23") (pin "1") (pinfunction "1_1") (pintype "passive"))
      (node (ref "U1") (pin "26") (pinfunction "PB13_26") (pintype "bidirectional"))
      (node (ref "U15") (pin "2") (pinfunction "I1_2") (pintype "input"))
    )
    (net (code "27") (name "ISENSE") (class "Default")
      (node (ref "C16") (pin "2") (pinfunction "2_2") (pintype "passive"))
      (node (ref "R123") (pin "1") (pinfunction "1_1") (pintype "passive"))
      (node (ref "U1") (pin "14") (pinfunction "PA4_14") (pintype "bidirectional"))
    )
    (net (code "28") (name "JMP0") (class "Default")
      (node (ref "J5") (pin "9") (pinfunction "9_9") (pintype "passive"))
      (node (ref "U1") (pin "19") (pinfunction "PB1_19") (pintype "bidirectional"))
    )
    (net (code "29") (name "JMP1") (class "Default")
      (node (ref "J5") (pin "7") (pinfunction "7_7") (pintype "passive"))
      (node (ref "U1") (pin "20") (pinfunction "PB2-BOOT1_20") (pintype "bidirectional"))
    )
    (net (code "30") (name "JMP2") (class "Default")
      (node (ref "J5") (pin "5") (pinfunction "5_5") (pintype "passive"))
      (node (ref "U1") (pin "21") (pinfunction "PB10_21") (pintype "bidirectional"))
    )
    (net (code "31") (name "JMP3") (class "Default")
      (node (ref "J5") (pin "3") (pinfunction "3_3") (pintype "passive"))
      (node (ref "U1") (pin "22") (pinfunction "PB11_22") (pintype "bidirectional"))
    )
    (net (code "32") (name "JMP4") (class "Default")
      (node (ref "J5") (pin "1") (pinfunction "1_1") (pintype "passive"))
      (node (ref "U1") (pin "25") (pinfunction "PB12_25") (pintype "bidirectional"))
    )
    (net (code "33") (name "LED0") (class "Default")
      (node (ref "R109") (pin "1") (pinfunction "1_1") (pintype "passive"))
      (node (ref "U1") (pin "16") (pinfunction "PA6_16") (pintype "bidirectional"))
    )
    (net (code "34") (name "LED1") (class "Default")
      (node (ref "R110") (pin "1") (pinfunction "1_1") (pintype "passive"))
      (node (ref "U1") (pin "17") (pinfunction "PA7_17") (pintype "bidirectional"))
    )
    (net (code "35") (name "LED2") (class "Default")
      (node (ref "R111") (pin "1") (pinfunction "1_1") (pintype "passive"))
      (node (ref "U1") (pin "18") (pinfunction "PB0_18") (pintype "bidirectional"))
    )
    (net (code "36") (name "LED_CAN") (class "Default")
      (node (ref "R21") (pin "1") (pinfunction "1_1") (pintype "passive"))
      (node (ref "U1") (pin "3") (pinfunction "PC14-OSC32_IN_3") (pintype "bidirectional"))
    )
    (net (code "37") (name "Net-(D9-PadA)") (class "Default")
      (node (ref "D9") (pin "A") (pinfunction "A_A") (pintype "passive"))
      (node (ref "R109") (pin "2") (pinfunction "2_2") (pintype "passive"))
    )
    (net (code "38") (name "Net-(D10-PadA)") (class "Default")
      (node (ref "D10") (pin "A") (pinfunction "A_A") (pintype "passive"))
      (node (ref "R110") (pin "2") (pinfunction "2_2") (pintype "passive"))
    )
    (net (code "39") (name "Net-(D11-PadA)") (class "Default")
      (node (ref "D11") (pin "A") (pinfunction "A_A") (pintype "passive"))
      (node (ref "R111") (pin "2") (pinfunction "2_2") (pintype "passive"))
    )
    (net (code "40") (name "Net-(F1-Pad2)") (class "Default")
      (node (ref "F1") (pin "2") (pinfunction "2_2") (pintype "passive"))
      (node (ref "J1") (pin "4") (pinfunction "4_4") (pintype "input"))
      (node (ref "J1") (pin "5") (pinfunction "5_5") (pintype "input"))
      (node (ref "R20") (pin "1") (pinfunction "1_1") (pintype "passive"))
    )
    (net (code "41") (name "Net-(J1-A-G)") (class "Default")
      (node (ref "J1") (pin "GA") (pinfunction "A-G_GA") (pintype "passive"))
      (node (ref "R20") (pin "2") (pinfunction "2_2") (pintype "passive"))
    )
    (net (code "42") (name "Net-(J1-A-Y)") (class "Default")
      (node (ref "J1") (pin "YA") (pinfunction "A-Y_YA") (pintype "passive"))
      (node (ref "R21") (pin "2") (pinfunction "2_2") (pintype "passive"))
    )
    (net (code "43") (name "Net-(J2-Pad3)") (class "Default")
      (node (ref "J2") (pin "3") (pinfunction "3_3") (pintype "passive"))
      (node (ref "R15") (pin "2") (pinfunction "2_2") (pintype "passive"))
    )
    (net (code "44") (name "Net-(J2-Pad4)") (class "Default")
      (node (ref "J2") (pin "4") (pinfunction "4_4") (pintype "passive"))
      (node (ref "R16") (pin "2") (pinfunction "2_2") (pintype "passive"))
    )
    (net (code "45") (name "Net-(J6-Pad2)") (class "Default")
      (node (ref "J6") (pin "2") (pinfunction "2_2") (pintype "passive"))
      (node (ref "R12") (pin "2") (pinfunction "2_2") (pintype "passive"))
    )
    (net (code "46") (name "Net-(Q1-GATE)") (class "Default")
      (node (ref "Q1") (pin "4") (pinfunction "GATE_4") (pintype "passive"))
      (node (ref "R1") (pin "2") (pinfunction "2_2") (pintype "passive"))
    )
    (net (code "47") (name "Net-(Q2-GATE)") (class "Default")
      (node (ref "Q2") (pin "4") (pinfunction "GATE_4") (pintype "passive"))
      (node (ref "R3") (pin "2") (pinfunction "2_2") (pintype "passive"))
    )
    (net (code "48") (name "Net-(Q3-GATE)") (class "Default")
      (node (ref "Q3") (pin "4") (pinfunction "GATE_4") (pintype "passive"))
      (node (ref "R2") (pin "2") (pinfunction "2_2") (pintype "passive"))
    )
    (net (code "49") (name "Net-(Q4-GATE)") (class "Default")
      (node (ref "Q4") (pin "4") (pinfunction "GATE_4") (pintype "passive"))
      (node (ref "R4") (pin "2") (pinfunction "2_2") (pintype "passive"))
    )
    (net (code "50") (name "Net-(U$1-3)") (class "Default")
      (node (ref "R24") (pin "2") (pinfunction "2_2") (pintype "passive"))
      (node (ref "U$1") (pin "P$3") (pinfunction "3_P$3") (pintype "bidirectional"))
    )
    (net (code "51") (name "Net-(U$1-4)") (class "Default")
      (node (ref "R17") (pin "2") (pinfunction "2_2") (pintype "passive"))
      (node (ref "U$1") (pin "P$4") (pinfunction "4_P$4") (pintype "bidirectional"))
    )
    (net (code "52") (name "Net-(U1-OSC_IN)") (class "Default")
      (node (ref "U1") (pin "5") (pinfunction "OSC_IN_5") (pintype "input"))
      (node (ref "X1") (pin "1") (pinfunction "1_1") (pintype "passive"))
    )
    (net (code "53") (name "Net-(U1-OSC_OUT)") (class "Default")
      (node (ref "U1") (pin "6") (pinfunction "OSC_OUT_6") (pintype "output"))
      (node (ref "X1") (pin "3") (pinfunction "3_3") (pintype "passive"))
    )
    (net (code "54") (name "Net-(U2-RXD)") (class "Default")
      (node (ref "U2") (pin "4") (pinfunction "RXD_4") (pintype "output"))
      (node (ref "U3") (pin "6") (pinfunction "B2_6") (pintype "output"))
    )
    (net (code "55") (name "Net-(U2-TXD)") (class "Default")
      (node (ref "U2") (pin "1") (pinfunction "TXD_1") (pintype "input"))
      (node (ref "U3") (pin "7") (pinfunction "B1_7") (pintype "output"))
    )
    (net (code "56") (name "Net-(U4-AC1)") (class "Default")
      (node (ref "R28") (pin "1") (pinfunction "1_1") (pintype "passive"))
      (node (ref "U4") (pin "1") (pinfunction "AC1_1") (pintype "passive"))
    )
    (net (code "57") (name "Net-(U5-DRV_HI)") (class "Default")
      (node (ref "R1") (pin "1") (pinfunction "1_1") (pintype "passive"))
      (node (ref "R5") (pin "2") (pinfunction "2_2") (pintype "passive"))
      (node (ref "U5") (pin "7") (pinfunction "DRV_HI_7") (pintype "output"))
    )
    (net (code "58") (name "Net-(U5-DRV_LO)") (class "Default")
      (node (ref "R3") (pin "1") (pinfunction "1_1") (pintype "passive"))
      (node (ref "R7") (pin "2") (pinfunction "2_2") (pintype "passive"))
      (node (ref "U5") (pin "5") (pinfunction "DRV_LO_5") (pintype "output"))
    )
    (net (code "59") (name "Net-(U5-VBOOT)") (class "Default")
      (node (ref "C9") (pin "1") (pinfunction "1_1") (pintype "passive"))
      (node (ref "D1") (pin "C") (pinfunction "C_C") (pintype "passive"))
      (node (ref "U5") (pin "8") (pinfunction "VBOOT_8") (pintype "power_in"))
    )
    (net (code "60") (name "Net-(U6-DRV_HI)") (class "Default")
      (node (ref "R2") (pin "1") (pinfunction "1_1") (pintype "passive"))
      (node (ref "R6") (pin "2") (pinfunction "2_2") (pintype "passive"))
      (node (ref "U6") (pin "7") (pinfunction "DRV_HI_7") (pintype "output"))
    )
    (net (code "61") (name "Net-(U6-DRV_LO)") (class "Default")
      (node (ref "R4") (pin "1") (pinfunction "1_1") (pintype "passive"))
      (node (ref "R8") (pin "2") (pinfunction "2_2") (pintype "passive"))
      (node (ref "U6") (pin "5") (pinfunction "DRV_LO_5") (pintype "output"))
    )
    (net (code "62") (name "Net-(U6-VBOOT)") (class "Default")
      (node (ref "C10") (pin "1") (pinfunction "1_1") (pintype "passive"))
      (node (ref "D4") (pin "C") (pinfunction "C_C") (pintype "passive"))
      (node (ref "U6") (pin "8") (pinfunction "VBOOT_8") (pintype "power_in"))
    )
    (net (code "63") (name "Net-(U7-IN+)") (class "Default")
      (node (ref "C14") (pin "2") (pinfunction "2_2") (pintype "passive"))
      (node (ref "R10") (pin "2") (pinfunction "2_2") (pintype "passive"))
      (node (ref "U7") (pin "4") (pinfunction "IN+_4") (pintype "passive"))
    )
    (net (code "64") (name "Net-(U7-IN-)") (class "Default")
      (node (ref "C14") (pin "1") (pinfunction "1_1") (pintype "passive"))
      (node (ref "R11") (pin "2") (pinfunction "2_2") (pintype "passive"))
      (node (ref "U7") (pin "5") (pinfunction "IN-_5") (pintype "passive"))
    )
    (net (code "65") (name "Net-(U7-OUT)") (class "Default")
      (node (ref "R123") (pin "2") (pinfunction "2_2") (pintype "passive"))
      (node (ref "U7") (pin "6") (pinfunction "OUT_6") (pintype "passive"))
    )
    (net (code "66") (name "SWCLK") (class "Default")
      (node (ref "J4") (pin "4") (pinfunction "4_4") (pintype "passive"))
      (node (ref "U1") (pin "37") (pinfunction "PA14-JTCK-SWCLK_37") (pintype "bidirectional"))
    )
    (net (code "67") (name "SWDIO") (class "Default")
      (node (ref "J4") (pin "6") (pinfunction "6_6") (pintype "passive"))
      (node (ref "U1") (pin "34") (pinfunction "PA13-JTMS-SWDIO_34") (pintype "bidirectional"))
    )
    (net (code "68") (name "UART_RX") (class "Default")
      (node (ref "J4") (pin "1") (pinfunction "1_1") (pintype "passive"))
      (node (ref "U1") (pin "43") (pinfunction "PB7_43") (pintype "bidirectional"))
    )
    (net (code "69") (name "UART_TX") (class "Default")
      (node (ref "J4") (pin "3") (pinfunction "3_3") (pintype "passive"))
      (node (ref "U1") (pin "42") (pinfunction "PB6_42") (pintype "bidirectional"))
    )
    (net (code "70") (name "VCC") (class "Default")
      (node (ref "C1") (pin "+") (pinfunction "+_+") (pintype "passive"))
      (node (ref "C11") (pin "1") (pinfunction "1_1") (pintype "passive"))
      (node (ref "C12") (pin "1") (pinfunction "1_1") (pintype "passive"))
      (node (ref "C2") (pin "+") (pinfunction "+_+") (pintype "passive"))
      (node (ref "C3") (pin "1") (pinfunction "1_1") (pintype "passive"))
      (node (ref "C5") (pin "1") (pinfunction "1_1") (pintype "passive"))
      (node (ref "C6") (pin "1") (pinfunction "1_1") (pintype "passive"))
      (node (ref "Q1") (pin "5") (pinfunction "DRAIN_5") (pintype "passive"))
      (node (ref "Q3") (pin "5") (pinfunction "DRAIN_5") (pintype "passive"))
      (node (ref "R13") (pin "2") (pinfunction "2_2") (pintype "passive"))
      (node (ref "U8") (pin "1") (pinfunction "VI_1") (pintype "input"))
    )
    (net (code "71") (name "VCS") (class "Default")
      (node (ref "C11") (pin "2") (pinfunction "2_2") (pintype "passive"))
      (node (ref "C12") (pin "2") (pinfunction "2_2") (pintype "passive"))
      (node (ref "C13") (pin "2") (pinfunction "2_2") (pintype "passive"))
      (node (ref "C5") (pin "2") (pinfunction "2_2") (pintype "passive"))
      (node (ref "C6") (pin "2") (pinfunction "2_2") (pintype "passive"))
      (node (ref "Q2") (pin "1") (pinfunction "SOURCE_1") (pintype "passive"))
      (node (ref "Q2") (pin "2") (pinfunction "SOURCE_2") (pintype "passive"))
      (node (ref "Q2") (pin "3") (pinfunction "SOURCE_3") (pintype "passive"))
      (node (ref "Q4") (pin "1") (pinfunction "SOURCE_1") (pintype "passive"))
      (node (ref "Q4") (pin "2") (pinfunction "SOURCE_2") (pintype "passive"))
      (node (ref "Q4") (pin "3") (pinfunction "SOURCE_3") (pintype "passive"))
      (node (ref "R7") (pin "1") (pinfunction "1_1") (pintype "passive"))
      (node (ref "R8") (pin "1") (pinfunction "1_1") (pintype "passive"))
      (node (ref "R9") (pin "2$1") (pinfunction "2_2$1") (pintype "passive"))
      (node (ref "R9") (pin "2$2") (pinfunction "2_2$2") (pintype "passive"))
    )
    (net (code "72") (name "VCS_B_N") (class "Default")
      (node (ref "R11") (pin "1") (pinfunction "1_1") (pintype "passive"))
      (node (ref "R9") (pin "1S") (pinfunction "1S_1S") (pintype "passive"))
    )
    (net (code "73") (name "VCS_B_P") (class "Default")
      (node (ref "R10") (pin "1") (pinfunction "1_1") (pintype "passive"))
      (node (ref "R9") (pin "2S") (pinfunction "2S_2S") (pintype "passive"))
    )
    (net (code "74") (name "VSENSE") (class "Default")
      (node (ref "C17") (pin "2") (pinfunction "2_2") (pintype "passive"))
      (node (ref "R13") (pin "1") (pinfunction "1_1") (pintype "passive"))
      (node (ref "R14") (pin "2") (pinfunction "2_2") (pintype "passive"))
      (node (ref "U1") (pin "15") (pinfunction "PA5_15") (pintype "bidirectional"))
    )
    (net (code "75") (name "unconnected-(U1-PA10-Pad31)") (class "Default")
      (node (ref "U1") (pin "31") (pinfunction "PA10_31") (pintype "bidirectional"))
    )
    (net (code "76") (name "unconnected-(U1-PA11-Pad32)") (class "Default")
      (node (ref "U1") (pin "32") (pinfunction "PA11_32") (pintype "bidirectional"))
    )
    (net (code "77") (name "unconnected-(U1-PA12-Pad33)") (class "Default")
      (node (ref "U1") (pin "33") (pinfunction "PA12_33") (pintype "bidirectional"))
    )
    (net (code "78") (name "unconnected-(U1-PA15-JTDI-Pad38)") (class "Default")
      (node (ref "U1") (pin "38") (pinfunction "PA15-JTDI_38") (pintype "bidirectional"))
    )
    (net (code "79") (name "unconnected-(U1-PB3-JTDO-Pad39)") (class "Default")
      (node (ref "U1") (pin "39") (pinfunction "PB3-JTDO_39") (pintype "bidirectional"))
    )
    (net (code "80") (name "unconnected-(U1-PB4-JNTRST-Pad40)") (class "Default")
      (node (ref "U1") (pin "40") (pinfunction "PB4-JNTRST_40") (pintype "bidirectional"))
    )
    (net (code "81") (name "unconnected-(U1-PB5-Pad41)") (class "Default")
      (node (ref "U1") (pin "41") (pinfunction "PB5_41") (pintype "bidirectional"))
    )
    (net (code "82") (name "unconnected-(U1-PB15-Pad28)") (class "Default")
      (node (ref "U1") (pin "28") (pinfunction "PB15_28") (pintype "bidirectional"))
    )
    (net (code "83") (name "unconnected-(U1-PC15-OSC32_OUT-Pad4)") (class "Default")
      (node (ref "U1") (pin "4") (pinfunction "PC15-OSC32_OUT_4") (pintype "bidirectional"))
    )
    (net (code "84") (name "unconnected-(U1-VBAT-Pad1)") (class "Default")
      (node (ref "U1") (pin "1") (pinfunction "VBAT_1") (pintype "passive"))
    )
    (net (code "85") (name "~{EMS_ISO}") (class "Default")
      (node (ref "J1") (pin "6") (pinfunction "6_6") (pintype "input"))
      (node (ref "R28") (pin "2") (pinfunction "2_2") (pintype "passive"))
    )
    (net (code "86") (name "~{EMS}") (class "Default")
      (node (ref "R30") (pin "2") (pinfunction "2_2") (pintype "passive"))
      (node (ref "U1") (pin "2") (pinfunction "PC13-TAMPER-RTC_2") (pintype "bidirectional"))
      (node (ref "U12") (pin "1") (pinfunction "I0_1") (pintype "input"))
      (node (ref "U13") (pin "1") (pinfunction "I0_1") (pintype "input"))
      (node (ref "U14") (pin "1") (pinfunction "I0_1") (pintype "input"))
      (node (ref "U15") (pin "1") (pinfunction "I0_1") (pintype "input"))
      (node (ref "U4") (pin "3") (pinfunction "E_3") (pintype "passive"))
    )
    (net (code "87") (name "~{RESET}") (class "Default")
      (node (ref "C22") (pin "2") (pinfunction "2_2") (pintype "passive"))
      (node (ref "S1") (pin "P$2") (pinfunction "2_P$2") (pintype "bidirectional"))
      (node (ref "U1") (pin "7") (pinfunction "NRST_7") (pintype "bidirectional"))
    )
  )
)
